# Headlightsv4.net
KiCad netlist of a schematic drawn in EAGLE
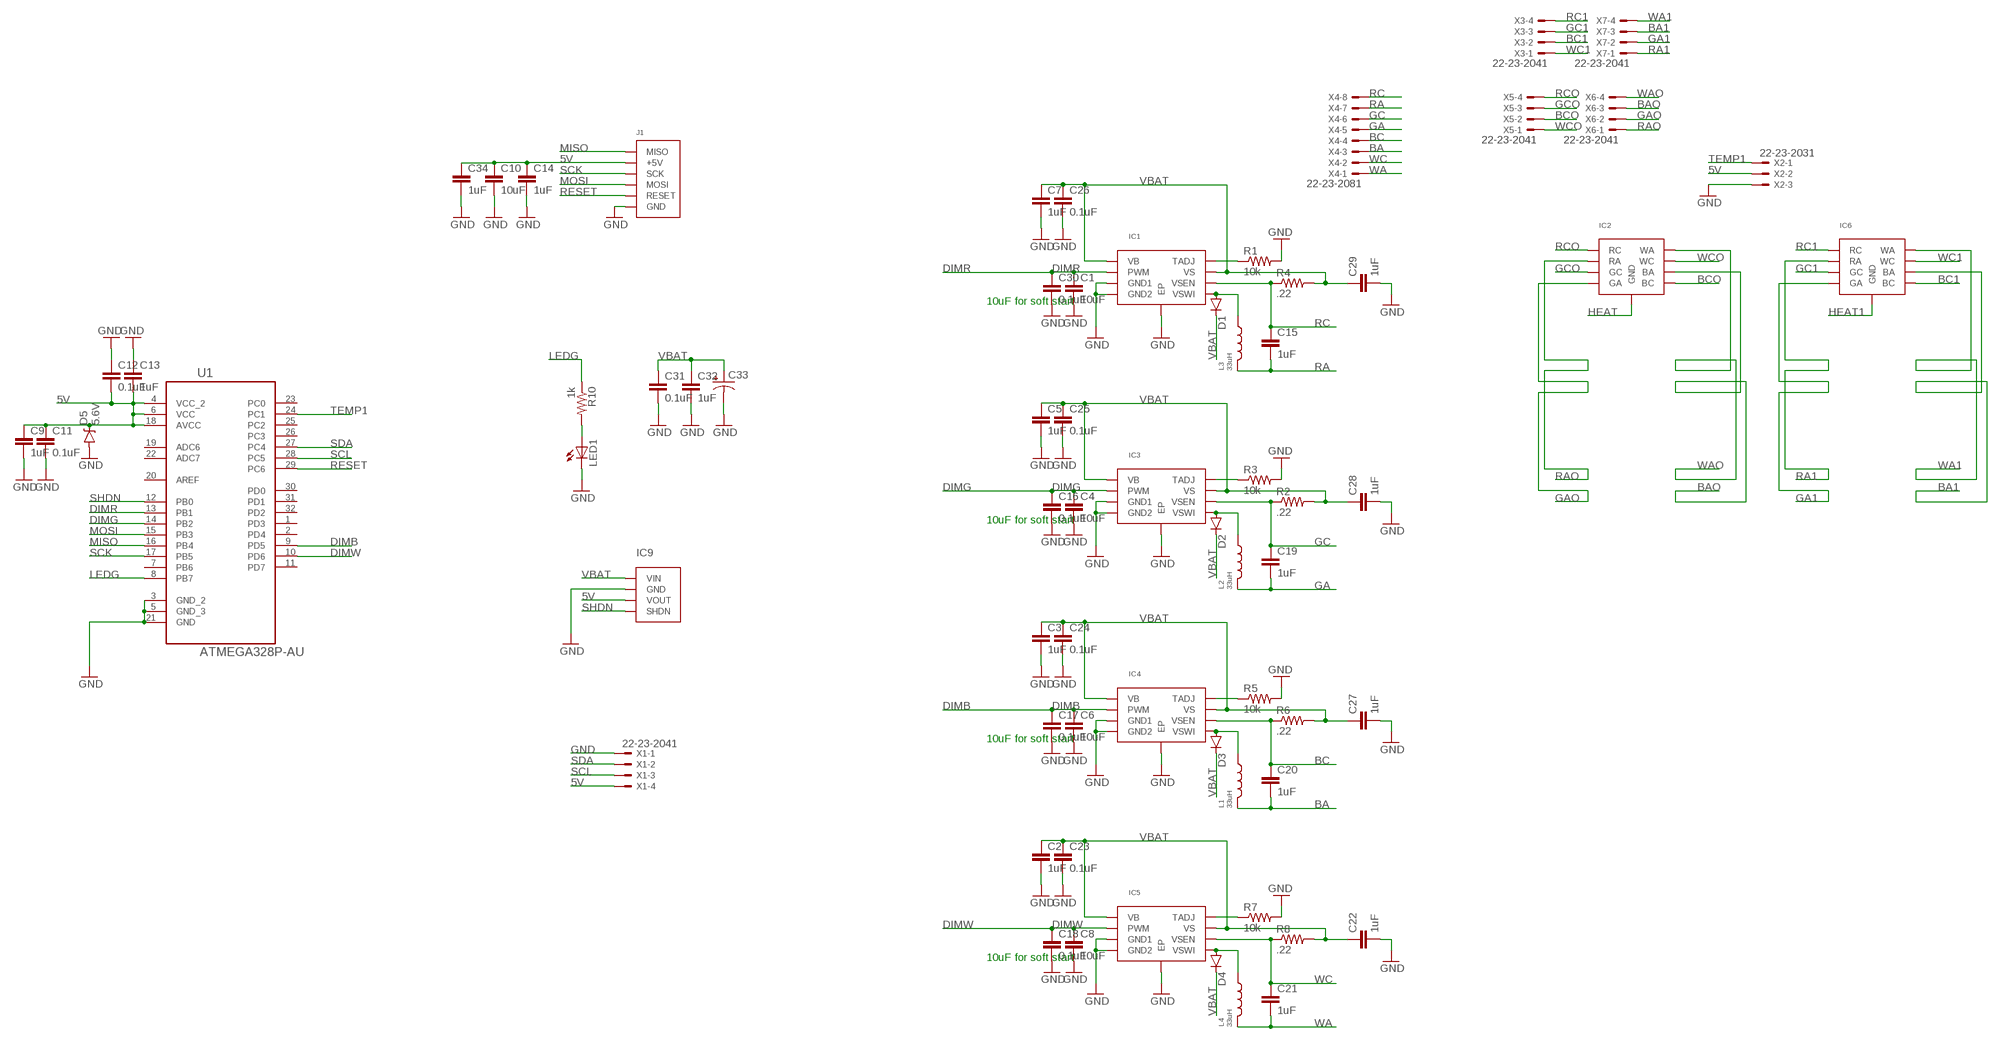
[diagram p0: schematic, sheet 1]

(export (version "E")
  (design (tool "Eeschema 10.0.6"))
  (components
    (comp (ref "C1")
      (value "10uF")
      (footprint "eagle-import:0805-CAP")
      (libsource (lib "eagle-import") (part "10UF10V10%(0805)"))
    )
    (comp (ref "C2")
      (value "1uF")
      (footprint "eagle-import:0805-CAP")
      (libsource (lib "eagle-import") (part "0.33UF-50V-10%(0805)"))
    )
    (comp (ref "C3")
      (value "1uF")
      (footprint "eagle-import:0805-CAP")
      (libsource (lib "eagle-import") (part "0.33UF-50V-10%(0805)"))
    )
    (comp (ref "C4")
      (value "10uF")
      (footprint "eagle-import:0805-CAP")
      (libsource (lib "eagle-import") (part "10UF10V10%(0805)"))
    )
    (comp (ref "C5")
      (value "1uF")
      (footprint "eagle-import:0805-CAP")
      (libsource (lib "eagle-import") (part "0.33UF-50V-10%(0805)"))
    )
    (comp (ref "C6")
      (value "10uF")
      (footprint "eagle-import:0805-CAP")
      (libsource (lib "eagle-import") (part "10UF10V10%(0805)"))
    )
    (comp (ref "C7")
      (value "1uF")
      (footprint "eagle-import:0805-CAP")
      (libsource (lib "eagle-import") (part "0.33UF-50V-10%(0805)"))
    )
    (comp (ref "C8")
      (value "10uF")
      (footprint "eagle-import:0805-CAP")
      (libsource (lib "eagle-import") (part "10UF10V10%(0805)"))
    )
    (comp (ref "C9")
      (value "1uF")
      (footprint "eagle-import:0805-CAP")
      (libsource (lib "eagle-import") (part "0.33UF-50V-10%(0805)"))
    )
    (comp (ref "C10")
      (value "10uF")
      (footprint "eagle-import:0805-CAP")
      (libsource (lib "eagle-import") (part "10UF10V10%(0805)"))
    )
    (comp (ref "C11")
      (value "0.1uF")
      (footprint "eagle-import:0805-CAP")
      (libsource (lib "eagle-import") (part "0.33UF-50V-10%(0805)"))
    )
    (comp (ref "C12")
      (value "0.1uF")
      (footprint "eagle-import:0805-CAP")
      (libsource (lib "eagle-import") (part "0.33UF-50V-10%(0805)"))
    )
    (comp (ref "C13")
      (value "1uF")
      (footprint "eagle-import:0805-CAP")
      (libsource (lib "eagle-import") (part "0.33UF-50V-10%(0805)"))
    )
    (comp (ref "C14")
      (value "1uF")
      (footprint "eagle-import:0805-CAP")
      (libsource (lib "eagle-import") (part "0.33UF-50V-10%(0805)"))
    )
    (comp (ref "C15")
      (value "1uF")
      (footprint "eagle-import:0805-CAP")
      (libsource (lib "eagle-import") (part "0.33UF-50V-10%(0805)"))
    )
    (comp (ref "C16")
      (value "0.1uF")
      (footprint "eagle-import:0805-CAP")
      (libsource (lib "eagle-import") (part "0.33UF-50V-10%(0805)"))
    )
    (comp (ref "C17")
      (value "0.1uF")
      (footprint "eagle-import:0805-CAP")
      (libsource (lib "eagle-import") (part "0.33UF-50V-10%(0805)"))
    )
    (comp (ref "C18")
      (value "0.1uF")
      (footprint "eagle-import:0805-CAP")
      (libsource (lib "eagle-import") (part "0.33UF-50V-10%(0805)"))
    )
    (comp (ref "C19")
      (value "1uF")
      (footprint "eagle-import:0805-CAP")
      (libsource (lib "eagle-import") (part "0.33UF-50V-10%(0805)"))
    )
    (comp (ref "C20")
      (value "1uF")
      (footprint "eagle-import:0805-CAP")
      (libsource (lib "eagle-import") (part "0.33UF-50V-10%(0805)"))
    )
    (comp (ref "C21")
      (value "1uF")
      (footprint "eagle-import:0805-CAP")
      (libsource (lib "eagle-import") (part "0.33UF-50V-10%(0805)"))
    )
    (comp (ref "C22")
      (value "1uF")
      (footprint "eagle-import:0805-CAP")
      (libsource (lib "eagle-import") (part "0.33UF-50V-10%(0805)"))
    )
    (comp (ref "C23")
      (value "0.1uF")
      (footprint "eagle-import:0805-CAP")
      (libsource (lib "eagle-import") (part "0.33UF-50V-10%(0805)"))
    )
    (comp (ref "C24")
      (value "0.1uF")
      (footprint "eagle-import:0805-CAP")
      (libsource (lib "eagle-import") (part "0.33UF-50V-10%(0805)"))
    )
    (comp (ref "C25")
      (value "0.1uF")
      (footprint "eagle-import:0805-CAP")
      (libsource (lib "eagle-import") (part "0.33UF-50V-10%(0805)"))
    )
    (comp (ref "C26")
      (value "0.1uF")
      (footprint "eagle-import:0805-CAP")
      (libsource (lib "eagle-import") (part "0.33UF-50V-10%(0805)"))
    )
    (comp (ref "C27")
      (value "1uF")
      (footprint "eagle-import:0805-CAP")
      (libsource (lib "eagle-import") (part "0.33UF-50V-10%(0805)"))
    )
    (comp (ref "C28")
      (value "1uF")
      (footprint "eagle-import:0805-CAP")
      (libsource (lib "eagle-import") (part "0.33UF-50V-10%(0805)"))
    )
    (comp (ref "C29")
      (value "1uF")
      (footprint "eagle-import:0805-CAP")
      (libsource (lib "eagle-import") (part "0.33UF-50V-10%(0805)"))
    )
    (comp (ref "C30")
      (value "0.1uF")
      (footprint "eagle-import:0805-CAP")
      (libsource (lib "eagle-import") (part "0.33UF-50V-10%(0805)"))
    )
    (comp (ref "C31")
      (value "0.1uF")
      (footprint "eagle-import:0805-CAP")
      (libsource (lib "eagle-import") (part "0.33UF-50V-10%(0805)"))
    )
    (comp (ref "C32")
      (value "1uF")
      (footprint "eagle-import:0805-CAP")
      (libsource (lib "eagle-import") (part "0.33UF-50V-10%(0805)"))
    )
    (comp (ref "C33")
      (value "CAP_POLF80")
      (footprint "eagle-import:NIPPON_F80")
      (libsource (lib "eagle-import") (part "CAP_POLF80"))
    )
    (comp (ref "C34")
      (value "1uF")
      (footprint "eagle-import:0805-CAP")
      (libsource (lib "eagle-import") (part "0.33UF-50V-10%(0805)"))
    )
    (comp (ref "D1")
      (value "DIODESMA-ALT")
      (footprint "eagle-import:SMA-DIODE_ALT")
      (libsource (lib "eagle-import") (part "DIODESMA-ALT"))
    )
    (comp (ref "D2")
      (value "DIODESMA-ALT")
      (footprint "eagle-import:SMA-DIODE_ALT")
      (libsource (lib "eagle-import") (part "DIODESMA-ALT"))
    )
    (comp (ref "D3")
      (value "DIODESMA-ALT")
      (footprint "eagle-import:SMA-DIODE_ALT")
      (libsource (lib "eagle-import") (part "DIODESMA-ALT"))
    )
    (comp (ref "D4")
      (value "DIODESMA-ALT")
      (footprint "eagle-import:SMA-DIODE_ALT")
      (libsource (lib "eagle-import") (part "DIODESMA-ALT"))
    )
    (comp (ref "D5")
      (value "5.6V")
      (footprint "eagle-import:SOD-323")
      (libsource (lib "eagle-import") (part "DIODE-ZENER5.6V"))
    )
    (comp (ref "IC1")
      (value "ILD6150_LED_DRIVER")
      (footprint "eagle-import:PG-DSO-8-27")
      (libsource (lib "eagle-import") (part "ILD6150_LED_DRIVER"))
    )
    (comp (ref "IC2")
      (value "LED_RGBW_CONF2")
      (footprint "eagle-import:LED_RGBW_CUSTOM")
      (libsource (lib "eagle-import") (part "LED_RGBW_CONF2"))
    )
    (comp (ref "IC3")
      (value "ILD6150_LED_DRIVER")
      (footprint "eagle-import:PG-DSO-8-27")
      (libsource (lib "eagle-import") (part "ILD6150_LED_DRIVER"))
    )
    (comp (ref "IC4")
      (value "ILD6150_LED_DRIVER")
      (footprint "eagle-import:PG-DSO-8-27")
      (libsource (lib "eagle-import") (part "ILD6150_LED_DRIVER"))
    )
    (comp (ref "IC5")
      (value "ILD6150_LED_DRIVER")
      (footprint "eagle-import:PG-DSO-8-27")
      (libsource (lib "eagle-import") (part "ILD6150_LED_DRIVER"))
    )
    (comp (ref "IC6")
      (value "LED_RGBW_CONF2")
      (footprint "eagle-import:LED_RGBW_CUSTOM")
      (libsource (lib "eagle-import") (part "LED_RGBW_CONF2"))
    )
    (comp (ref "IC9")
      (value "5VBUCK_DANNY_CUSTOM_PCB")
      (footprint "eagle-import:4PIN_.1'")
      (libsource (lib "eagle-import") (part "5VBUCK_DANNY_CUSTOM_PCB"))
    )
    (comp (ref "J1")
      (value "ISPHEADER")
      (footprint "eagle-import:2X3PIN_.1'")
      (libsource (lib "eagle-import") (part "ISPHEADER"))
    )
    (comp (ref "L1")
      (value "33uH")
      (footprint "eagle-import:8X8MM_IND")
      (libsource (lib "eagle-import") (part "CHIP_IND"))
    )
    (comp (ref "L2")
      (value "33uH")
      (footprint "eagle-import:8X8MM_IND")
      (libsource (lib "eagle-import") (part "CHIP_IND"))
    )
    (comp (ref "L3")
      (value "33uH")
      (footprint "eagle-import:8X8MM_IND")
      (libsource (lib "eagle-import") (part "CHIP_IND"))
    )
    (comp (ref "L4")
      (value "33uH")
      (footprint "eagle-import:8X8MM_IND")
      (libsource (lib "eagle-import") (part "CHIP_IND"))
    )
    (comp (ref "LED1")
      (value "LEDCHIPLED_0805")
      (footprint "eagle-import:CHIPLED_0805")
      (libsource (lib "eagle-import") (part "LEDCHIPLED_0805"))
    )
    (comp (ref "R1")
      (value "10k")
      (footprint "eagle-import:0805")
      (libsource (lib "eagle-import") (part "0.3OHM-1/8W-1%(0805)"))
    )
    (comp (ref "R2")
      (value ".22")
      (footprint "eagle-import:1206")
      (libsource (lib "eagle-import") (part "RESISTOR1206"))
    )
    (comp (ref "R3")
      (value "10k")
      (footprint "eagle-import:0805")
      (libsource (lib "eagle-import") (part "0.3OHM-1/8W-1%(0805)"))
    )
    (comp (ref "R4")
      (value ".22")
      (footprint "eagle-import:1206")
      (libsource (lib "eagle-import") (part "RESISTOR1206"))
    )
    (comp (ref "R5")
      (value "10k")
      (footprint "eagle-import:0805")
      (libsource (lib "eagle-import") (part "0.3OHM-1/8W-1%(0805)"))
    )
    (comp (ref "R6")
      (value ".22")
      (footprint "eagle-import:1206")
      (libsource (lib "eagle-import") (part "RESISTOR1206"))
    )
    (comp (ref "R7")
      (value "10k")
      (footprint "eagle-import:0805")
      (libsource (lib "eagle-import") (part "0.3OHM-1/8W-1%(0805)"))
    )
    (comp (ref "R8")
      (value ".22")
      (footprint "eagle-import:1206")
      (libsource (lib "eagle-import") (part "RESISTOR1206"))
    )
    (comp (ref "R10")
      (value "1k")
      (footprint "eagle-import:0805")
      (libsource (lib "eagle-import") (part "0.3OHM-1/8W-1%(0805)"))
    )
    (comp (ref "U1")
      (value "ATMEGA328P-AU")
      (footprint "eagle-import:QFP80P900X900X120-32N")
      (libsource (lib "eagle-import") (part "ATMEGA328P-AU"))
    )
    (comp (ref "X1")
      (value "22-23-2041")
      (footprint "eagle-import:22-23-2041")
      (fields (field (name "MF") "MOLEX"))
      (libsource (lib "eagle-import") (part "22-23-2041"))
    )
    (comp (ref "X2")
      (value "22-23-2031")
      (footprint "eagle-import:22-23-2031")
      (fields (field (name "MF") "MOLEX"))
      (libsource (lib "eagle-import") (part "22-23-2031"))
    )
    (comp (ref "X3")
      (value "22-23-2041")
      (footprint "eagle-import:22-23-2041")
      (fields (field (name "MF") "MOLEX"))
      (libsource (lib "eagle-import") (part "22-23-2041"))
    )
    (comp (ref "X4")
      (value "22-23-2081")
      (footprint "eagle-import:22-23-2081")
      (fields (field (name "MF") "MOLEX"))
      (libsource (lib "eagle-import") (part "22-23-2081"))
    )
    (comp (ref "X5")
      (value "22-23-2041")
      (footprint "eagle-import:22-23-2041")
      (fields (field (name "MF") "MOLEX"))
      (libsource (lib "eagle-import") (part "22-23-2041"))
    )
    (comp (ref "X6")
      (value "22-23-2041")
      (footprint "eagle-import:22-23-2041")
      (fields (field (name "MF") "MOLEX"))
      (libsource (lib "eagle-import") (part "22-23-2041"))
    )
    (comp (ref "X7")
      (value "22-23-2041")
      (footprint "eagle-import:22-23-2041")
      (fields (field (name "MF") "MOLEX"))
      (libsource (lib "eagle-import") (part "22-23-2041"))
    )
  )
  (nets
    (net (code "1") (name "/5V") (class "Default")
      (node (ref "C10") (pin "1") (pinfunction "1_1") (pintype "passive"))
      (node (ref "C11") (pin "1") (pinfunction "1_1") (pintype "passive"))
      (node (ref "C12") (pin "2") (pinfunction "2_2") (pintype "passive"))
      (node (ref "C13") (pin "2") (pinfunction "2_2") (pintype "passive"))
      (node (ref "C14") (pin "1") (pinfunction "1_1") (pintype "passive"))
      (node (ref "C34") (pin "1") (pinfunction "1_1") (pintype "passive"))
      (node (ref "C9") (pin "1") (pinfunction "1_1") (pintype "passive"))
      (node (ref "D5") (pin "C") (pinfunction "C_C") (pintype "passive"))
      (node (ref "IC9") (pin "P$3") (pinfunction "VOUT_P$3") (pintype "bidirectional"))
      (node (ref "J1") (pin "P$2") (pinfunction "+5V_P$2") (pintype "bidirectional"))
      (node (ref "U1") (pin "18") (pinfunction "AVCC_18") (pintype "power_in"))
      (node (ref "U1") (pin "4") (pinfunction "VCC_2_4") (pintype "power_in"))
      (node (ref "U1") (pin "6") (pinfunction "VCC_6") (pintype "power_in"))
      (node (ref "X1") (pin "4") (pinfunction "S_4") (pintype "passive"))
      (node (ref "X2") (pin "2") (pinfunction "S_2") (pintype "passive"))
    )
    (net (code "2") (name "/BA") (class "Default")
      (node (ref "C20") (pin "2") (pinfunction "2_2") (pintype "passive"))
      (node (ref "L1") (pin "P$1") (pinfunction "P$1_P$1") (pintype "bidirectional"))
      (node (ref "X4") (pin "3") (pinfunction "S_3") (pintype "passive"))
    )
    (net (code "3") (name "/BA1") (class "Default")
      (node (ref "IC6") (pin "6") (pinfunction "BA_6") (pintype "bidirectional"))
      (node (ref "X7") (pin "3") (pinfunction "S_3") (pintype "passive"))
    )
    (net (code "4") (name "/BAO") (class "Default")
      (node (ref "IC2") (pin "6") (pinfunction "BA_6") (pintype "bidirectional"))
      (node (ref "X6") (pin "3") (pinfunction "S_3") (pintype "passive"))
    )
    (net (code "5") (name "/BC") (class "Default")
      (node (ref "C20") (pin "1") (pinfunction "1_1") (pintype "passive"))
      (node (ref "IC4") (pin "P$6") (pinfunction "VSEN_P$6") (pintype "bidirectional"))
      (node (ref "R6") (pin "1") (pinfunction "1_1") (pintype "passive"))
      (node (ref "X4") (pin "4") (pinfunction "S_4") (pintype "passive"))
    )
    (net (code "6") (name "/BC1") (class "Default")
      (node (ref "IC6") (pin "5") (pinfunction "BC_5") (pintype "bidirectional"))
      (node (ref "X3") (pin "2") (pinfunction "S_2") (pintype "passive"))
    )
    (net (code "7") (name "/BCO") (class "Default")
      (node (ref "IC2") (pin "5") (pinfunction "BC_5") (pintype "bidirectional"))
      (node (ref "X5") (pin "2") (pinfunction "S_2") (pintype "passive"))
    )
    (net (code "8") (name "/DIMB") (class "Default")
      (node (ref "C17") (pin "1") (pinfunction "1_1") (pintype "passive"))
      (node (ref "C6") (pin "1") (pinfunction "1_1") (pintype "passive"))
      (node (ref "IC4") (pin "P$2") (pinfunction "PWM_P$2") (pintype "bidirectional"))
      (node (ref "U1") (pin "9") (pinfunction "PD5_9") (pintype "bidirectional"))
    )
    (net (code "9") (name "/DIMG") (class "Default")
      (node (ref "C16") (pin "1") (pinfunction "1_1") (pintype "passive"))
      (node (ref "C4") (pin "1") (pinfunction "1_1") (pintype "passive"))
      (node (ref "IC3") (pin "P$2") (pinfunction "PWM_P$2") (pintype "bidirectional"))
      (node (ref "U1") (pin "14") (pinfunction "PB2_14") (pintype "bidirectional"))
    )
    (net (code "10") (name "/DIMR") (class "Default")
      (node (ref "C1") (pin "1") (pinfunction "1_1") (pintype "passive"))
      (node (ref "C30") (pin "1") (pinfunction "1_1") (pintype "passive"))
      (node (ref "IC1") (pin "P$2") (pinfunction "PWM_P$2") (pintype "bidirectional"))
      (node (ref "U1") (pin "13") (pinfunction "PB1_13") (pintype "bidirectional"))
    )
    (net (code "11") (name "/DIMW") (class "Default")
      (node (ref "C18") (pin "1") (pinfunction "1_1") (pintype "passive"))
      (node (ref "C8") (pin "1") (pinfunction "1_1") (pintype "passive"))
      (node (ref "IC5") (pin "P$2") (pinfunction "PWM_P$2") (pintype "bidirectional"))
      (node (ref "U1") (pin "10") (pinfunction "PD6_10") (pintype "bidirectional"))
    )
    (net (code "12") (name "/GA") (class "Default")
      (node (ref "C19") (pin "2") (pinfunction "2_2") (pintype "passive"))
      (node (ref "L2") (pin "P$1") (pinfunction "P$1_P$1") (pintype "bidirectional"))
      (node (ref "X4") (pin "5") (pinfunction "S_5") (pintype "passive"))
    )
    (net (code "13") (name "/GA1") (class "Default")
      (node (ref "IC6") (pin "4") (pinfunction "GA_4") (pintype "bidirectional"))
      (node (ref "X7") (pin "2") (pinfunction "S_2") (pintype "passive"))
    )
    (net (code "14") (name "/GAO") (class "Default")
      (node (ref "IC2") (pin "4") (pinfunction "GA_4") (pintype "bidirectional"))
      (node (ref "X6") (pin "2") (pinfunction "S_2") (pintype "passive"))
    )
    (net (code "15") (name "/GC") (class "Default")
      (node (ref "C19") (pin "1") (pinfunction "1_1") (pintype "passive"))
      (node (ref "IC3") (pin "P$6") (pinfunction "VSEN_P$6") (pintype "bidirectional"))
      (node (ref "R2") (pin "1") (pinfunction "1_1") (pintype "passive"))
      (node (ref "X4") (pin "6") (pinfunction "S_6") (pintype "passive"))
    )
    (net (code "16") (name "/GC1") (class "Default")
      (node (ref "IC6") (pin "3") (pinfunction "GC_3") (pintype "bidirectional"))
      (node (ref "X3") (pin "3") (pinfunction "S_3") (pintype "passive"))
    )
    (net (code "17") (name "/GCO") (class "Default")
      (node (ref "IC2") (pin "3") (pinfunction "GC_3") (pintype "bidirectional"))
      (node (ref "X5") (pin "3") (pinfunction "S_3") (pintype "passive"))
    )
    (net (code "18") (name "/HEAT") (class "Default")
      (node (ref "IC2") (pin "9") (pinfunction "GND_9") (pintype "bidirectional"))
    )
    (net (code "19") (name "/HEAT1") (class "Default")
      (node (ref "IC6") (pin "9") (pinfunction "GND_9") (pintype "bidirectional"))
    )
    (net (code "20") (name "/LEDG") (class "Default")
      (node (ref "R10") (pin "1") (pinfunction "1_1") (pintype "passive"))
      (node (ref "U1") (pin "8") (pinfunction "PB7_8") (pintype "bidirectional"))
    )
    (net (code "21") (name "/MISO") (class "Default")
      (node (ref "J1") (pin "P$1") (pinfunction "MISO_P$1") (pintype "bidirectional"))
      (node (ref "U1") (pin "16") (pinfunction "PB4_16") (pintype "bidirectional"))
    )
    (net (code "22") (name "/MOSI") (class "Default")
      (node (ref "J1") (pin "P$4") (pinfunction "MOSI_P$4") (pintype "bidirectional"))
      (node (ref "U1") (pin "15") (pinfunction "PB3_15") (pintype "bidirectional"))
    )
    (net (code "23") (name "/RA") (class "Default")
      (node (ref "C15") (pin "2") (pinfunction "2_2") (pintype "passive"))
      (node (ref "L3") (pin "P$1") (pinfunction "P$1_P$1") (pintype "bidirectional"))
      (node (ref "X4") (pin "7") (pinfunction "S_7") (pintype "passive"))
    )
    (net (code "24") (name "/RA1") (class "Default")
      (node (ref "IC6") (pin "2") (pinfunction "RA_2") (pintype "bidirectional"))
      (node (ref "X7") (pin "1") (pinfunction "S_1") (pintype "passive"))
    )
    (net (code "25") (name "/RAO") (class "Default")
      (node (ref "IC2") (pin "2") (pinfunction "RA_2") (pintype "bidirectional"))
      (node (ref "X6") (pin "1") (pinfunction "S_1") (pintype "passive"))
    )
    (net (code "26") (name "/RC") (class "Default")
      (node (ref "C15") (pin "1") (pinfunction "1_1") (pintype "passive"))
      (node (ref "IC1") (pin "P$6") (pinfunction "VSEN_P$6") (pintype "bidirectional"))
      (node (ref "R4") (pin "1") (pinfunction "1_1") (pintype "passive"))
      (node (ref "X4") (pin "8") (pinfunction "S_8") (pintype "passive"))
    )
    (net (code "27") (name "/RC1") (class "Default")
      (node (ref "IC6") (pin "1") (pinfunction "RC_1") (pintype "bidirectional"))
      (node (ref "X3") (pin "4") (pinfunction "S_4") (pintype "passive"))
    )
    (net (code "28") (name "/RCO") (class "Default")
      (node (ref "IC2") (pin "1") (pinfunction "RC_1") (pintype "bidirectional"))
      (node (ref "X5") (pin "4") (pinfunction "S_4") (pintype "passive"))
    )
    (net (code "29") (name "/RESET") (class "Default")
      (node (ref "J1") (pin "P$5") (pinfunction "RESET_P$5") (pintype "bidirectional"))
      (node (ref "U1") (pin "29") (pinfunction "PC6_29") (pintype "bidirectional"))
    )
    (net (code "30") (name "/SCK") (class "Default")
      (node (ref "J1") (pin "P$3") (pinfunction "SCK_P$3") (pintype "bidirectional"))
      (node (ref "U1") (pin "17") (pinfunction "PB5_17") (pintype "bidirectional"))
    )
    (net (code "31") (name "/SCL") (class "Default")
      (node (ref "U1") (pin "28") (pinfunction "PC5_28") (pintype "bidirectional"))
      (node (ref "X1") (pin "3") (pinfunction "S_3") (pintype "passive"))
    )
    (net (code "32") (name "/SDA") (class "Default")
      (node (ref "U1") (pin "27") (pinfunction "PC4_27") (pintype "bidirectional"))
      (node (ref "X1") (pin "2") (pinfunction "S_2") (pintype "passive"))
    )
    (net (code "33") (name "/SHDN") (class "Default")
      (node (ref "IC9") (pin "P$4") (pinfunction "SHDN_P$4") (pintype "bidirectional"))
      (node (ref "U1") (pin "12") (pinfunction "PB0_12") (pintype "bidirectional"))
    )
    (net (code "34") (name "/TEMP1") (class "Default")
      (node (ref "U1") (pin "24") (pinfunction "PC1_24") (pintype "bidirectional"))
      (node (ref "X2") (pin "1") (pinfunction "S_1") (pintype "passive"))
    )
    (net (code "35") (name "/VBAT") (class "Default")
      (node (ref "C2") (pin "1") (pinfunction "1_1") (pintype "passive"))
      (node (ref "C22") (pin "1") (pinfunction "1_1") (pintype "passive"))
      (node (ref "C23") (pin "1") (pinfunction "1_1") (pintype "passive"))
      (node (ref "C24") (pin "1") (pinfunction "1_1") (pintype "passive"))
      (node (ref "C25") (pin "1") (pinfunction "1_1") (pintype "passive"))
      (node (ref "C26") (pin "1") (pinfunction "1_1") (pintype "passive"))
      (node (ref "C27") (pin "1") (pinfunction "1_1") (pintype "passive"))
      (node (ref "C28") (pin "1") (pinfunction "1_1") (pintype "passive"))
      (node (ref "C29") (pin "1") (pinfunction "1_1") (pintype "passive"))
      (node (ref "C3") (pin "1") (pinfunction "1_1") (pintype "passive"))
      (node (ref "C31") (pin "1") (pinfunction "1_1") (pintype "passive"))
      (node (ref "C32") (pin "1") (pinfunction "1_1") (pintype "passive"))
      (node (ref "C33") (pin "+") (pinfunction "+_+") (pintype "passive"))
      (node (ref "C5") (pin "1") (pinfunction "1_1") (pintype "passive"))
      (node (ref "C7") (pin "1") (pinfunction "1_1") (pintype "passive"))
      (node (ref "D1") (pin "C") (pinfunction "C_C") (pintype "passive"))
      (node (ref "D2") (pin "C") (pinfunction "C_C") (pintype "passive"))
      (node (ref "D3") (pin "C") (pinfunction "C_C") (pintype "passive"))
      (node (ref "D4") (pin "C") (pinfunction "C_C") (pintype "passive"))
      (node (ref "IC1") (pin "P$1") (pinfunction "VB_P$1") (pintype "bidirectional"))
      (node (ref "IC1") (pin "P$7") (pinfunction "VS_P$7") (pintype "bidirectional"))
      (node (ref "IC3") (pin "P$1") (pinfunction "VB_P$1") (pintype "bidirectional"))
      (node (ref "IC3") (pin "P$7") (pinfunction "VS_P$7") (pintype "bidirectional"))
      (node (ref "IC4") (pin "P$1") (pinfunction "VB_P$1") (pintype "bidirectional"))
      (node (ref "IC4") (pin "P$7") (pinfunction "VS_P$7") (pintype "bidirectional"))
      (node (ref "IC5") (pin "P$1") (pinfunction "VB_P$1") (pintype "bidirectional"))
      (node (ref "IC5") (pin "P$7") (pinfunction "VS_P$7") (pintype "bidirectional"))
      (node (ref "IC9") (pin "P$1") (pinfunction "VIN_P$1") (pintype "bidirectional"))
      (node (ref "R2") (pin "2") (pinfunction "2_2") (pintype "passive"))
      (node (ref "R4") (pin "2") (pinfunction "2_2") (pintype "passive"))
      (node (ref "R6") (pin "2") (pinfunction "2_2") (pintype "passive"))
      (node (ref "R8") (pin "2") (pinfunction "2_2") (pintype "passive"))
    )
    (net (code "36") (name "/WA") (class "Default")
      (node (ref "C21") (pin "2") (pinfunction "2_2") (pintype "passive"))
      (node (ref "L4") (pin "P$1") (pinfunction "P$1_P$1") (pintype "bidirectional"))
      (node (ref "X4") (pin "1") (pinfunction "S_1") (pintype "passive"))
    )
    (net (code "37") (name "/WA1") (class "Default")
      (node (ref "IC6") (pin "8") (pinfunction "WA_8") (pintype "bidirectional"))
      (node (ref "X7") (pin "4") (pinfunction "S_4") (pintype "passive"))
    )
    (net (code "38") (name "/WAO") (class "Default")
      (node (ref "IC2") (pin "8") (pinfunction "WA_8") (pintype "bidirectional"))
      (node (ref "X6") (pin "4") (pinfunction "S_4") (pintype "passive"))
    )
    (net (code "39") (name "/WC") (class "Default")
      (node (ref "C21") (pin "1") (pinfunction "1_1") (pintype "passive"))
      (node (ref "IC5") (pin "P$6") (pinfunction "VSEN_P$6") (pintype "bidirectional"))
      (node (ref "R8") (pin "1") (pinfunction "1_1") (pintype "passive"))
      (node (ref "X4") (pin "2") (pinfunction "S_2") (pintype "passive"))
    )
    (net (code "40") (name "/WC1") (class "Default")
      (node (ref "IC6") (pin "7") (pinfunction "WC_7") (pintype "bidirectional"))
      (node (ref "X3") (pin "1") (pinfunction "S_1") (pintype "passive"))
    )
    (net (code "41") (name "/WCO") (class "Default")
      (node (ref "IC2") (pin "7") (pinfunction "WC_7") (pintype "bidirectional"))
      (node (ref "X5") (pin "1") (pinfunction "S_1") (pintype "passive"))
    )
    (net (code "42") (name "GND") (class "Default")
      (node (ref "C1") (pin "2") (pinfunction "2_2") (pintype "passive"))
      (node (ref "C10") (pin "2") (pinfunction "2_2") (pintype "passive"))
      (node (ref "C11") (pin "2") (pinfunction "2_2") (pintype "passive"))
      (node (ref "C12") (pin "1") (pinfunction "1_1") (pintype "passive"))
      (node (ref "C13") (pin "1") (pinfunction "1_1") (pintype "passive"))
      (node (ref "C14") (pin "2") (pinfunction "2_2") (pintype "passive"))
      (node (ref "C16") (pin "2") (pinfunction "2_2") (pintype "passive"))
      (node (ref "C17") (pin "2") (pinfunction "2_2") (pintype "passive"))
      (node (ref "C18") (pin "2") (pinfunction "2_2") (pintype "passive"))
      (node (ref "C2") (pin "2") (pinfunction "2_2") (pintype "passive"))
      (node (ref "C22") (pin "2") (pinfunction "2_2") (pintype "passive"))
      (node (ref "C23") (pin "2") (pinfunction "2_2") (pintype "passive"))
      (node (ref "C24") (pin "2") (pinfunction "2_2") (pintype "passive"))
      (node (ref "C25") (pin "2") (pinfunction "2_2") (pintype "passive"))
      (node (ref "C26") (pin "2") (pinfunction "2_2") (pintype "passive"))
      (node (ref "C27") (pin "2") (pinfunction "2_2") (pintype "passive"))
      (node (ref "C28") (pin "2") (pinfunction "2_2") (pintype "passive"))
      (node (ref "C29") (pin "2") (pinfunction "2_2") (pintype "passive"))
      (node (ref "C3") (pin "2") (pinfunction "2_2") (pintype "passive"))
      (node (ref "C30") (pin "2") (pinfunction "2_2") (pintype "passive"))
      (node (ref "C31") (pin "2") (pinfunction "2_2") (pintype "passive"))
      (node (ref "C32") (pin "2") (pinfunction "2_2") (pintype "passive"))
      (node (ref "C33") (pin "-") (pinfunction "-_-") (pintype "passive"))
      (node (ref "C34") (pin "2") (pinfunction "2_2") (pintype "passive"))
      (node (ref "C4") (pin "2") (pinfunction "2_2") (pintype "passive"))
      (node (ref "C5") (pin "2") (pinfunction "2_2") (pintype "passive"))
      (node (ref "C6") (pin "2") (pinfunction "2_2") (pintype "passive"))
      (node (ref "C7") (pin "2") (pinfunction "2_2") (pintype "passive"))
      (node (ref "C8") (pin "2") (pinfunction "2_2") (pintype "passive"))
      (node (ref "C9") (pin "2") (pinfunction "2_2") (pintype "passive"))
      (node (ref "D5") (pin "A") (pinfunction "A_A") (pintype "passive"))
      (node (ref "IC1") (pin "P$3") (pinfunction "GND1_P$3") (pintype "bidirectional"))
      (node (ref "IC1") (pin "P$4") (pinfunction "GND2_P$4") (pintype "bidirectional"))
      (node (ref "IC1") (pin "P$9") (pinfunction "EP_P$9") (pintype "bidirectional"))
      (node (ref "IC3") (pin "P$3") (pinfunction "GND1_P$3") (pintype "bidirectional"))
      (node (ref "IC3") (pin "P$4") (pinfunction "GND2_P$4") (pintype "bidirectional"))
      (node (ref "IC3") (pin "P$9") (pinfunction "EP_P$9") (pintype "bidirectional"))
      (node (ref "IC4") (pin "P$3") (pinfunction "GND1_P$3") (pintype "bidirectional"))
      (node (ref "IC4") (pin "P$4") (pinfunction "GND2_P$4") (pintype "bidirectional"))
      (node (ref "IC4") (pin "P$9") (pinfunction "EP_P$9") (pintype "bidirectional"))
      (node (ref "IC5") (pin "P$3") (pinfunction "GND1_P$3") (pintype "bidirectional"))
      (node (ref "IC5") (pin "P$4") (pinfunction "GND2_P$4") (pintype "bidirectional"))
      (node (ref "IC5") (pin "P$9") (pinfunction "EP_P$9") (pintype "bidirectional"))
      (node (ref "IC9") (pin "P$2") (pinfunction "GND_P$2") (pintype "bidirectional"))
      (node (ref "J1") (pin "P$6") (pinfunction "GND_P$6") (pintype "bidirectional"))
      (node (ref "LED1") (pin "C") (pinfunction "C_C") (pintype "passive"))
      (node (ref "R1") (pin "2") (pinfunction "2_2") (pintype "passive"))
      (node (ref "R3") (pin "2") (pinfunction "2_2") (pintype "passive"))
      (node (ref "R5") (pin "2") (pinfunction "2_2") (pintype "passive"))
      (node (ref "R7") (pin "2") (pinfunction "2_2") (pintype "passive"))
      (node (ref "U1") (pin "21") (pinfunction "GND_21") (pintype "passive"))
      (node (ref "U1") (pin "3") (pinfunction "GND_2_3") (pintype "passive"))
      (node (ref "U1") (pin "5") (pinfunction "GND_3_5") (pintype "passive"))
      (node (ref "X1") (pin "1") (pinfunction "S_1") (pintype "passive"))
      (node (ref "X2") (pin "3") (pinfunction "S_3") (pintype "passive"))
    )
    (net (code "43") (name "Net-(IC1-TADJ)") (class "Default")
      (node (ref "IC1") (pin "P$8") (pinfunction "TADJ_P$8") (pintype "bidirectional"))
      (node (ref "R1") (pin "1") (pinfunction "1_1") (pintype "passive"))
    )
    (net (code "44") (name "Net-(IC1-VSWI)") (class "Default")
      (node (ref "D1") (pin "A") (pinfunction "A_A") (pintype "passive"))
      (node (ref "IC1") (pin "P$5") (pinfunction "VSWI_P$5") (pintype "bidirectional"))
      (node (ref "L3") (pin "P$2") (pinfunction "P$2_P$2") (pintype "bidirectional"))
    )
    (net (code "45") (name "Net-(IC3-TADJ)") (class "Default")
      (node (ref "IC3") (pin "P$8") (pinfunction "TADJ_P$8") (pintype "bidirectional"))
      (node (ref "R3") (pin "1") (pinfunction "1_1") (pintype "passive"))
    )
    (net (code "46") (name "Net-(IC3-VSWI)") (class "Default")
      (node (ref "D2") (pin "A") (pinfunction "A_A") (pintype "passive"))
      (node (ref "IC3") (pin "P$5") (pinfunction "VSWI_P$5") (pintype "bidirectional"))
      (node (ref "L2") (pin "P$2") (pinfunction "P$2_P$2") (pintype "bidirectional"))
    )
    (net (code "47") (name "Net-(IC4-TADJ)") (class "Default")
      (node (ref "IC4") (pin "P$8") (pinfunction "TADJ_P$8") (pintype "bidirectional"))
      (node (ref "R5") (pin "1") (pinfunction "1_1") (pintype "passive"))
    )
    (net (code "48") (name "Net-(IC4-VSWI)") (class "Default")
      (node (ref "D3") (pin "A") (pinfunction "A_A") (pintype "passive"))
      (node (ref "IC4") (pin "P$5") (pinfunction "VSWI_P$5") (pintype "bidirectional"))
      (node (ref "L1") (pin "P$2") (pinfunction "P$2_P$2") (pintype "bidirectional"))
    )
    (net (code "49") (name "Net-(IC5-TADJ)") (class "Default")
      (node (ref "IC5") (pin "P$8") (pinfunction "TADJ_P$8") (pintype "bidirectional"))
      (node (ref "R7") (pin "1") (pinfunction "1_1") (pintype "passive"))
    )
    (net (code "50") (name "Net-(IC5-VSWI)") (class "Default")
      (node (ref "D4") (pin "A") (pinfunction "A_A") (pintype "passive"))
      (node (ref "IC5") (pin "P$5") (pinfunction "VSWI_P$5") (pintype "bidirectional"))
      (node (ref "L4") (pin "P$2") (pinfunction "P$2_P$2") (pintype "bidirectional"))
    )
    (net (code "51") (name "Net-(LED1-PadA)") (class "Default")
      (node (ref "LED1") (pin "A") (pinfunction "A_A") (pintype "passive"))
      (node (ref "R10") (pin "2") (pinfunction "2_2") (pintype "passive"))
    )
    (net (code "52") (name "unconnected-(U1-ADC6-Pad19)") (class "Default")
      (node (ref "U1") (pin "19") (pinfunction "ADC6_19") (pintype "input"))
    )
    (net (code "53") (name "unconnected-(U1-ADC7-Pad22)") (class "Default")
      (node (ref "U1") (pin "22") (pinfunction "ADC7_22") (pintype "input"))
    )
    (net (code "54") (name "unconnected-(U1-AREF-Pad20)") (class "Default")
      (node (ref "U1") (pin "20") (pinfunction "AREF_20") (pintype "input"))
    )
    (net (code "55") (name "unconnected-(U1-PB6-Pad7)") (class "Default")
      (node (ref "U1") (pin "7") (pinfunction "PB6_7") (pintype "bidirectional"))
    )
    (net (code "56") (name "unconnected-(U1-PC0-Pad23)") (class "Default")
      (node (ref "U1") (pin "23") (pinfunction "PC0_23") (pintype "bidirectional"))
    )
    (net (code "57") (name "unconnected-(U1-PC2-Pad25)") (class "Default")
      (node (ref "U1") (pin "25") (pinfunction "PC2_25") (pintype "bidirectional"))
    )
    (net (code "58") (name "unconnected-(U1-PC3-Pad26)") (class "Default")
      (node (ref "U1") (pin "26") (pinfunction "PC3_26") (pintype "bidirectional"))
    )
    (net (code "59") (name "unconnected-(U1-PD0-Pad30)") (class "Default")
      (node (ref "U1") (pin "30") (pinfunction "PD0_30") (pintype "bidirectional"))
    )
    (net (code "60") (name "unconnected-(U1-PD1-Pad31)") (class "Default")
      (node (ref "U1") (pin "31") (pinfunction "PD1_31") (pintype "bidirectional"))
    )
    (net (code "61") (name "unconnected-(U1-PD2-Pad32)") (class "Default")
      (node (ref "U1") (pin "32") (pinfunction "PD2_32") (pintype "bidirectional"))
    )
    (net (code "62") (name "unconnected-(U1-PD3-Pad1)") (class "Default")
      (node (ref "U1") (pin "1") (pinfunction "PD3_1") (pintype "bidirectional"))
    )
    (net (code "63") (name "unconnected-(U1-PD4-Pad2)") (class "Default")
      (node (ref "U1") (pin "2") (pinfunction "PD4_2") (pintype "bidirectional"))
    )
    (net (code "64") (name "unconnected-(U1-PD7-Pad11)") (class "Default")
      (node (ref "U1") (pin "11") (pinfunction "PD7_11") (pintype "bidirectional"))
    )
  )
)
